# AIM2_-_GPS_Multiplexing_REVB.net
KiCad netlist of a schematic drawn in Altium Designer
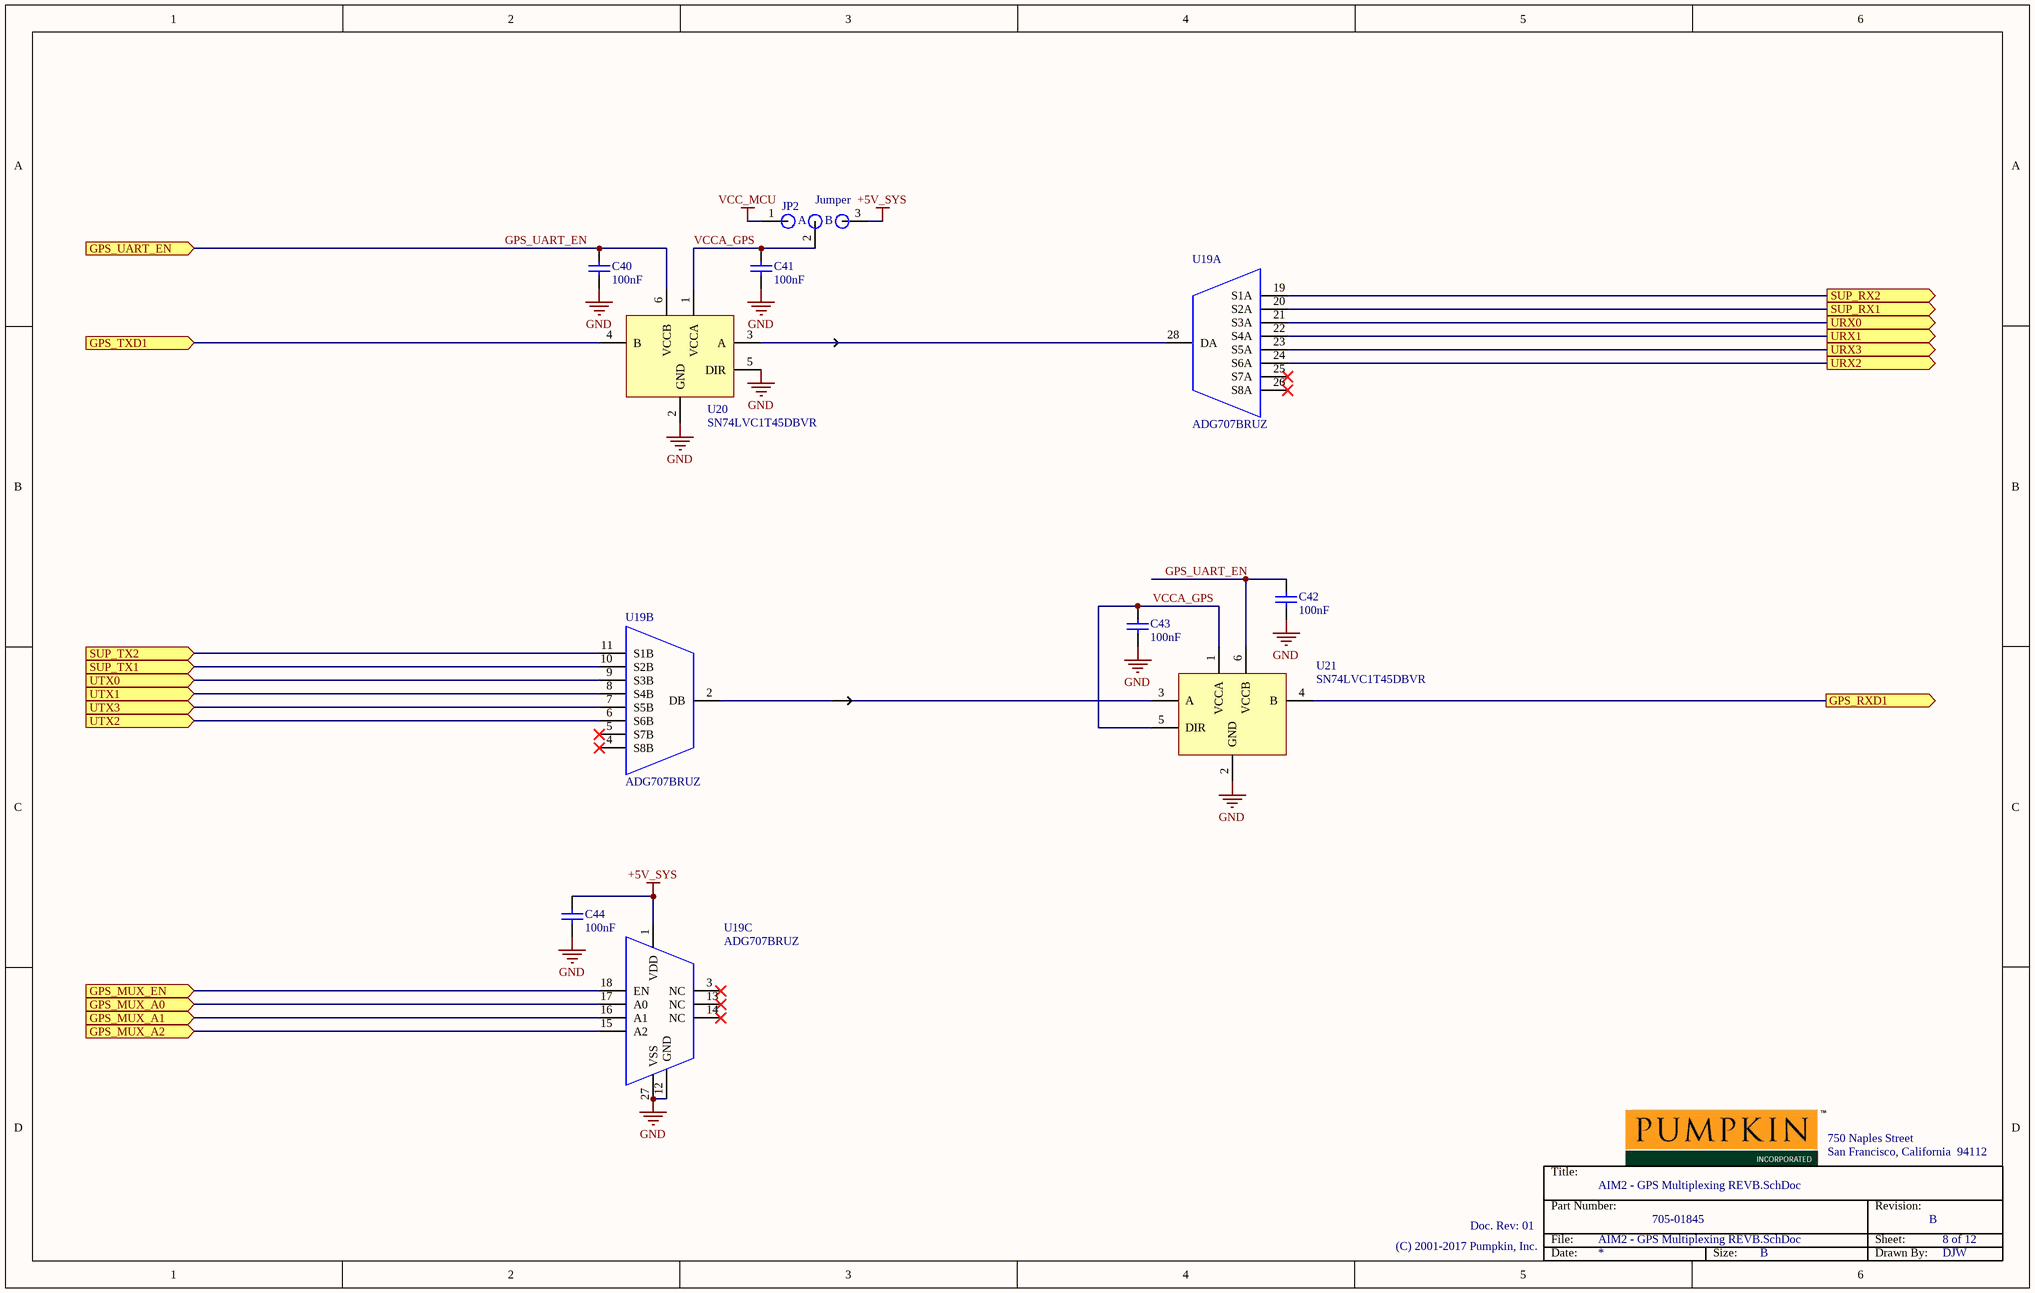
[diagram p0: AIM2 - GPS Multiplexing REVB.SchDoc]

(export (version "E")
  (design (tool "Eeschema 10.0.6"))
  (components
    (comp (ref "C40")
      (value "100nF")
      (footprint "0603 CAP")
      (description "Capacitor 100nF 0603 X7R 50V 5%")
      (libsource (lib "Supernova passives") (part "Capacitor 100nF 0603"))
    )
    (comp (ref "C41")
      (value "100nF")
      (footprint "0603 CAP")
      (description "Capacitor 100nF 0603 X7R 50V 5%")
      (libsource (lib "Supernova passives") (part "Capacitor 100nF 0603"))
    )
    (comp (ref "C42")
      (value "100nF")
      (footprint "0603 CAP")
      (description "Capacitor 100nF 0603 X7R 50V 5%")
      (libsource (lib "Supernova passives") (part "Capacitor 100nF 0603"))
    )
    (comp (ref "C43")
      (value "100nF")
      (footprint "0603 CAP")
      (description "Capacitor 100nF 0603 X7R 50V 5%")
      (libsource (lib "Supernova passives") (part "Capacitor 100nF 0603"))
    )
    (comp (ref "C44")
      (value "100nF")
      (footprint "0603 CAP")
      (description "Capacitor 100nF 0603 X7R 50V 5%")
      (libsource (lib "Supernova passives") (part "Capacitor 100nF 0603"))
    )
    (comp (ref "JP2")
      (value "Jumper")
      (footprint "0805 RES 2 way jumper - 1")
      (description "Jumper 0805 2 pos")
      (libsource (lib "Supernova passives") (part "Jumper 2 way 0805"))
    )
    (comp (ref "U19")
      (value "ADG707BRUZ")
      (footprint "28-TSSOP")
      (description "IC Multiplexer 2x 8:1")
      (libsource (lib "Supernova") (part "ADG707BRUZ"))
    )
    (comp (ref "U20")
      (value "SN74LVC1T45DBVR")
      (footprint "SOT23-6")
      (description "IC Logic Isolator 1 channel")
      (libsource (lib "Supernova") (part "SN74LVC1T45DBVR"))
    )
    (comp (ref "U21")
      (value "SN74LVC1T45DBVR")
      (footprint "SOT23-6")
      (description "IC Logic Isolator 1 channel")
      (libsource (lib "") (part "SN74LVC1T45DBVR_1"))
    )
  )
  (nets
    (net (code "1") (name "+5V_SYS") (class "Default")
      (node (ref "C44") (pin "2") (pinfunction "2_2") (pintype "passive"))
      (node (ref "JP2") (pin "3") (pinfunction "5_3") (pintype "passive"))
      (node (ref "U19") (pin "1") (pinfunction "VDD_1") (pintype "passive"))
    )
    (net (code "2") (name "/GPS_MUX_A0") (class "Default")
      (node (ref "U19") (pin "17") (pinfunction "A0_17") (pintype "passive"))
    )
    (net (code "3") (name "/GPS_MUX_A1") (class "Default")
      (node (ref "U19") (pin "16") (pinfunction "A1_16") (pintype "passive"))
    )
    (net (code "4") (name "/GPS_MUX_A2") (class "Default")
      (node (ref "U19") (pin "15") (pinfunction "A2_15") (pintype "passive"))
    )
    (net (code "5") (name "/GPS_MUX_EN") (class "Default")
      (node (ref "U19") (pin "18") (pinfunction "EN_18") (pintype "passive"))
    )
    (net (code "6") (name "/GPS_RXD1") (class "Default")
      (node (ref "U21") (pin "4") (pinfunction "B_4") (pintype "passive"))
    )
    (net (code "7") (name "/GPS_TXD1") (class "Default")
      (node (ref "U20") (pin "4") (pinfunction "B_4") (pintype "passive"))
    )
    (net (code "8") (name "/GPS_UART_EN") (class "Default")
      (node (ref "C40") (pin "2") (pinfunction "2_2") (pintype "passive"))
      (node (ref "C42") (pin "2") (pinfunction "2_2") (pintype "passive"))
      (node (ref "U20") (pin "6") (pinfunction "VCCB_6") (pintype "passive"))
      (node (ref "U21") (pin "6") (pinfunction "VCCB_6") (pintype "passive"))
    )
    (net (code "9") (name "/SUP_RX1") (class "Default")
      (node (ref "U19") (pin "20") (pinfunction "S2A_20") (pintype "passive"))
    )
    (net (code "10") (name "/SUP_RX2") (class "Default")
      (node (ref "U19") (pin "19") (pinfunction "S1A_19") (pintype "passive"))
    )
    (net (code "11") (name "/SUP_TX1") (class "Default")
      (node (ref "U19") (pin "10") (pinfunction "S2B_10") (pintype "passive"))
    )
    (net (code "12") (name "/SUP_TX2") (class "Default")
      (node (ref "U19") (pin "11") (pinfunction "S1B_11") (pintype "passive"))
    )
    (net (code "13") (name "/URX0") (class "Default")
      (node (ref "U19") (pin "21") (pinfunction "S3A_21") (pintype "passive"))
    )
    (net (code "14") (name "/URX1") (class "Default")
      (node (ref "U19") (pin "22") (pinfunction "S4A_22") (pintype "passive"))
    )
    (net (code "15") (name "/URX2") (class "Default")
      (node (ref "U19") (pin "24") (pinfunction "S6A_24") (pintype "passive"))
    )
    (net (code "16") (name "/URX3") (class "Default")
      (node (ref "U19") (pin "23") (pinfunction "S5A_23") (pintype "passive"))
    )
    (net (code "17") (name "/UTX0") (class "Default")
      (node (ref "U19") (pin "9") (pinfunction "S3B_9") (pintype "passive"))
    )
    (net (code "18") (name "/UTX1") (class "Default")
      (node (ref "U19") (pin "8") (pinfunction "S4B_8") (pintype "passive"))
    )
    (net (code "19") (name "/UTX2") (class "Default")
      (node (ref "U19") (pin "6") (pinfunction "S6B_6") (pintype "passive"))
    )
    (net (code "20") (name "/UTX3") (class "Default")
      (node (ref "U19") (pin "7") (pinfunction "S5B_7") (pintype "passive"))
    )
    (net (code "21") (name "/VCCA_GPS") (class "Default")
      (node (ref "C41") (pin "2") (pinfunction "2_2") (pintype "passive"))
      (node (ref "C43") (pin "2") (pinfunction "2_2") (pintype "passive"))
      (node (ref "JP2") (pin "2") (pinfunction "5_2") (pintype "passive"))
      (node (ref "U20") (pin "1") (pinfunction "VCCA_1") (pintype "passive"))
      (node (ref "U21") (pin "1") (pinfunction "VCCA_1") (pintype "passive"))
      (node (ref "U21") (pin "5") (pinfunction "DIR_5") (pintype "passive"))
    )
    (net (code "22") (name "GND") (class "Default")
      (node (ref "C40") (pin "1") (pinfunction "1_1") (pintype "passive"))
      (node (ref "C41") (pin "1") (pinfunction "1_1") (pintype "passive"))
      (node (ref "C42") (pin "1") (pinfunction "1_1") (pintype "passive"))
      (node (ref "C43") (pin "1") (pinfunction "1_1") (pintype "passive"))
      (node (ref "C44") (pin "1") (pinfunction "1_1") (pintype "passive"))
      (node (ref "U19") (pin "12") (pinfunction "GND_12") (pintype "passive"))
      (node (ref "U19") (pin "27") (pinfunction "VSS_27") (pintype "passive"))
      (node (ref "U20") (pin "2") (pinfunction "GND_2") (pintype "passive"))
      (node (ref "U20") (pin "5") (pinfunction "DIR_5") (pintype "passive"))
      (node (ref "U21") (pin "2") (pinfunction "GND_2") (pintype "passive"))
    )
    (net (code "23") (name "Net-(U19A-DA)") (class "Default")
      (node (ref "U19") (pin "28") (pinfunction "DA_28") (pintype "passive"))
      (node (ref "U20") (pin "3") (pinfunction "A_3") (pintype "passive"))
    )
    (net (code "24") (name "Net-(U19B-DB)") (class "Default")
      (node (ref "U19") (pin "2") (pinfunction "DB_2") (pintype "passive"))
      (node (ref "U21") (pin "3") (pinfunction "A_3") (pintype "passive"))
    )
    (net (code "25") (name "VCC_MCU") (class "Default")
      (node (ref "JP2") (pin "1") (pinfunction "5_1") (pintype "passive"))
    )
    (net (code "26") (name "unconnected-(U19A-S7A-Pad25)") (class "Default")
      (node (ref "U19") (pin "25") (pinfunction "S7A_25") (pintype "passive+no_connect"))
    )
    (net (code "27") (name "unconnected-(U19A-S8A-Pad26)") (class "Default")
      (node (ref "U19") (pin "26") (pinfunction "S8A_26") (pintype "passive+no_connect"))
    )
    (net (code "28") (name "unconnected-(U19B-S7B-Pad5)") (class "Default")
      (node (ref "U19") (pin "5") (pinfunction "S7B_5") (pintype "passive+no_connect"))
    )
    (net (code "29") (name "unconnected-(U19B-S8B-Pad4)") (class "Default")
      (node (ref "U19") (pin "4") (pinfunction "S8B_4") (pintype "passive+no_connect"))
    )
    (net (code "30") (name "unconnected-(U19C-NC-Pad3)") (class "Default")
      (node (ref "U19") (pin "3") (pinfunction "NC_3") (pintype "passive+no_connect"))
    )
    (net (code "31") (name "unconnected-(U19C-NC-Pad13)") (class "Default")
      (node (ref "U19") (pin "13") (pinfunction "NC_13") (pintype "passive+no_connect"))
    )
    (net (code "32") (name "unconnected-(U19C-NC-Pad14)") (class "Default")
      (node (ref "U19") (pin "14") (pinfunction "NC_14") (pintype "passive+no_connect"))
    )
  )
)
